# transfer.net
KiCad netlist of a schematic drawn in EAGLE
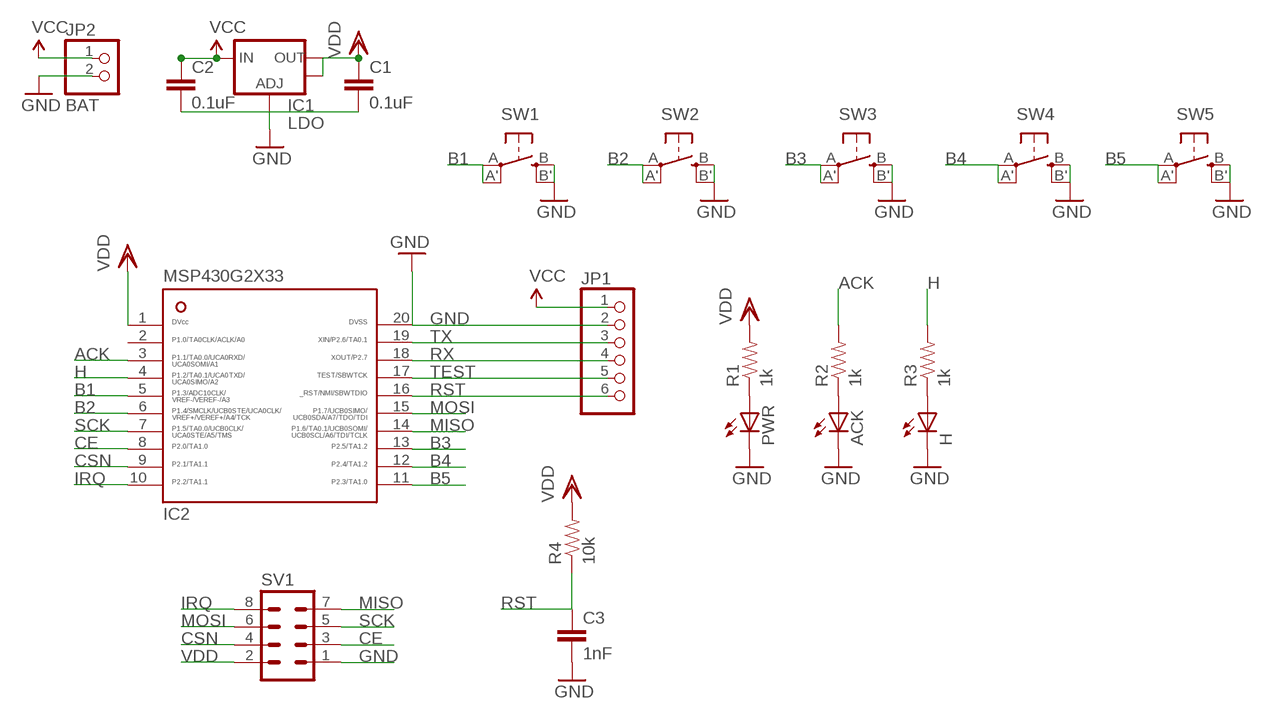
[diagram p0: schematic, sheet 1]

(export (version "E")
  (design (tool "Eeschema 10.0.6"))
  (components
    (comp (ref "ACK")
      (value "LEDCHIP-LED0805")
      (footprint "eagle-import:CHIP-LED0805")
      (libsource (lib "eagle-import") (part "LEDCHIP-LED0805"))
    )
    (comp (ref "C1")
      (value "0.1uF")
      (footprint "eagle-import:0603-CAP")
      (libsource (lib "eagle-import") (part "0.1UF-25V(+80/-20%)(0603)"))
    )
    (comp (ref "C2")
      (value "0.1uF")
      (footprint "eagle-import:0603-CAP")
      (libsource (lib "eagle-import") (part "0.1UF-25V(+80/-20%)(0603)"))
    )
    (comp (ref "C3")
      (value "1nF")
      (footprint "eagle-import:0603-CAP")
      (libsource (lib "eagle-import") (part "0.1UF-25V(+80/-20%)(0603)"))
    )
    (comp (ref "H")
      (value "LEDCHIP-LED0805")
      (footprint "eagle-import:CHIP-LED0805")
      (libsource (lib "eagle-import") (part "LEDCHIP-LED0805"))
    )
    (comp (ref "IC1")
      (value "LDO")
      (footprint "eagle-import:SOT223")
      (libsource (lib "eagle-import") (part "V_REG_LM1117SOT223"))
    )
    (comp (ref "IC2")
      (value "MSP430")
      (footprint "eagle-import:PW20")
      (libsource (lib "eagle-import") (part "MSP430G2X33-20PW20"))
    )
    (comp (ref "JP1")
      (value "PINHD-1X6")
      (footprint "eagle-import:1X06")
      (libsource (lib "eagle-import") (part "PINHD-1X6"))
    )
    (comp (ref "JP2")
      (value "BAT")
      (footprint "eagle-import:1X02")
      (libsource (lib "eagle-import") (part "PINHD-1X2"))
    )
    (comp (ref "PWR")
      (value "LEDCHIP-LED0805")
      (footprint "eagle-import:CHIP-LED0805")
      (libsource (lib "eagle-import") (part "LEDCHIP-LED0805"))
    )
    (comp (ref "R1")
      (value "1k")
      (footprint "eagle-import:0805")
      (libsource (lib "eagle-import") (part "0.22OHM1/4W1%(0805)"))
    )
    (comp (ref "R2")
      (value "1k")
      (footprint "eagle-import:0805")
      (libsource (lib "eagle-import") (part "0.22OHM1/4W1%(0805)"))
    )
    (comp (ref "R3")
      (value "1k")
      (footprint "eagle-import:0805")
      (libsource (lib "eagle-import") (part "0.22OHM1/4W1%(0805)"))
    )
    (comp (ref "R4")
      (value "10k")
      (footprint "eagle-import:0805")
      (libsource (lib "eagle-import") (part "0.22OHM1/4W1%(0805)"))
    )
    (comp (ref "SV1")
      (value "MA04-2")
      (footprint "eagle-import:MA04-2")
      (libsource (lib "eagle-import") (part "MA04-2"))
    )
    (comp (ref "SW1")
      (value "SPST_TACT-EVQQ2")
      (footprint "eagle-import:EVQ-Q2")
      (libsource (lib "eagle-import") (part "SPST_TACT-EVQQ2"))
    )
    (comp (ref "SW2")
      (value "SPST_TACT-EVQQ2")
      (footprint "eagle-import:EVQ-Q2")
      (libsource (lib "eagle-import") (part "SPST_TACT-EVQQ2"))
    )
    (comp (ref "SW3")
      (value "SPST_TACT-EVQQ2")
      (footprint "eagle-import:EVQ-Q2")
      (libsource (lib "eagle-import") (part "SPST_TACT-EVQQ2"))
    )
    (comp (ref "SW4")
      (value "SPST_TACT-EVQQ2")
      (footprint "eagle-import:EVQ-Q2")
      (libsource (lib "eagle-import") (part "SPST_TACT-EVQQ2"))
    )
    (comp (ref "SW5")
      (value "SPST_TACT-EVQQ2")
      (footprint "eagle-import:EVQ-Q2")
      (libsource (lib "eagle-import") (part "SPST_TACT-EVQQ2"))
    )
  )
  (nets
    (net (code "1") (name "/ACK") (class "Default")
      (node (ref "IC2") (pin "3") (pinfunction "3_3") (pintype "bidirectional"))
      (node (ref "R2") (pin "2") (pinfunction "2_2") (pintype "passive"))
    )
    (net (code "2") (name "/B1") (class "Default")
      (node (ref "IC2") (pin "5") (pinfunction "5_5") (pintype "bidirectional"))
      (node (ref "SW1") (pin "A") (pinfunction "P_A") (pintype "passive"))
      (node (ref "SW1") (pin "A'") (pinfunction "P1_A'") (pintype "passive"))
    )
    (net (code "3") (name "/B2") (class "Default")
      (node (ref "IC2") (pin "6") (pinfunction "6_6") (pintype "bidirectional"))
      (node (ref "SW2") (pin "A") (pinfunction "P_A") (pintype "passive"))
      (node (ref "SW2") (pin "A'") (pinfunction "P1_A'") (pintype "passive"))
    )
    (net (code "4") (name "/B3") (class "Default")
      (node (ref "IC2") (pin "13") (pinfunction "13_13") (pintype "bidirectional"))
      (node (ref "SW3") (pin "A") (pinfunction "P_A") (pintype "passive"))
      (node (ref "SW3") (pin "A'") (pinfunction "P1_A'") (pintype "passive"))
    )
    (net (code "5") (name "/B4") (class "Default")
      (node (ref "IC2") (pin "12") (pinfunction "12_12") (pintype "bidirectional"))
      (node (ref "SW4") (pin "A") (pinfunction "P_A") (pintype "passive"))
      (node (ref "SW4") (pin "A'") (pinfunction "P1_A'") (pintype "passive"))
    )
    (net (code "6") (name "/B5") (class "Default")
      (node (ref "IC2") (pin "11") (pinfunction "11_11") (pintype "bidirectional"))
      (node (ref "SW5") (pin "A") (pinfunction "P_A") (pintype "passive"))
      (node (ref "SW5") (pin "A'") (pinfunction "P1_A'") (pintype "passive"))
    )
    (net (code "7") (name "/CE") (class "Default")
      (node (ref "IC2") (pin "8") (pinfunction "8_8") (pintype "bidirectional"))
      (node (ref "SV1") (pin "3") (pinfunction "3_3") (pintype "passive"))
    )
    (net (code "8") (name "/CSN") (class "Default")
      (node (ref "IC2") (pin "9") (pinfunction "9_9") (pintype "bidirectional"))
      (node (ref "SV1") (pin "4") (pinfunction "4_4") (pintype "passive"))
    )
    (net (code "9") (name "/H") (class "Default")
      (node (ref "IC2") (pin "4") (pinfunction "4_4") (pintype "bidirectional"))
      (node (ref "R3") (pin "2") (pinfunction "2_2") (pintype "passive"))
    )
    (net (code "10") (name "/IRQ") (class "Default")
      (node (ref "IC2") (pin "10") (pinfunction "10_10") (pintype "bidirectional"))
      (node (ref "SV1") (pin "8") (pinfunction "8_8") (pintype "passive"))
    )
    (net (code "11") (name "/MISO") (class "Default")
      (node (ref "IC2") (pin "14") (pinfunction "14_14") (pintype "bidirectional"))
      (node (ref "SV1") (pin "7") (pinfunction "7_7") (pintype "passive"))
    )
    (net (code "12") (name "/MOSI") (class "Default")
      (node (ref "IC2") (pin "15") (pinfunction "15_15") (pintype "bidirectional"))
      (node (ref "SV1") (pin "6") (pinfunction "6_6") (pintype "passive"))
    )
    (net (code "13") (name "/RST") (class "Default")
      (node (ref "C3") (pin "1") (pinfunction "1_1") (pintype "passive"))
      (node (ref "IC2") (pin "16") (pinfunction "16_16") (pintype "bidirectional"))
      (node (ref "JP1") (pin "6") (pinfunction "6_6") (pintype "passive"))
      (node (ref "R4") (pin "1") (pinfunction "1_1") (pintype "passive"))
    )
    (net (code "14") (name "/RX") (class "Default")
      (node (ref "IC2") (pin "18") (pinfunction "18_18") (pintype "bidirectional"))
      (node (ref "JP1") (pin "4") (pinfunction "4_4") (pintype "passive"))
    )
    (net (code "15") (name "/SCK") (class "Default")
      (node (ref "IC2") (pin "7") (pinfunction "7_7") (pintype "bidirectional"))
      (node (ref "SV1") (pin "5") (pinfunction "5_5") (pintype "passive"))
    )
    (net (code "16") (name "/TEST") (class "Default")
      (node (ref "IC2") (pin "17") (pinfunction "17_17") (pintype "bidirectional"))
      (node (ref "JP1") (pin "5") (pinfunction "5_5") (pintype "passive"))
    )
    (net (code "17") (name "/TX") (class "Default")
      (node (ref "IC2") (pin "19") (pinfunction "19_19") (pintype "bidirectional"))
      (node (ref "JP1") (pin "3") (pinfunction "3_3") (pintype "passive"))
    )
    (net (code "18") (name "GND") (class "Default")
      (node (ref "ACK") (pin "C") (pinfunction "C_C") (pintype "passive"))
      (node (ref "C1") (pin "2") (pinfunction "2_2") (pintype "passive"))
      (node (ref "C2") (pin "2") (pinfunction "2_2") (pintype "passive"))
      (node (ref "C3") (pin "2") (pinfunction "2_2") (pintype "passive"))
      (node (ref "H") (pin "C") (pinfunction "C_C") (pintype "passive"))
      (node (ref "IC1") (pin "1") (pinfunction "ADJ_1") (pintype "input"))
      (node (ref "IC2") (pin "20") (pinfunction "20_20") (pintype "bidirectional"))
      (node (ref "JP1") (pin "2") (pinfunction "2_2") (pintype "passive"))
      (node (ref "JP2") (pin "2") (pinfunction "2_2") (pintype "passive"))
      (node (ref "PWR") (pin "C") (pinfunction "C_C") (pintype "passive"))
      (node (ref "SV1") (pin "1") (pinfunction "1_1") (pintype "passive"))
      (node (ref "SW1") (pin "B") (pinfunction "S_B") (pintype "passive"))
      (node (ref "SW1") (pin "B'") (pinfunction "S1_B'") (pintype "passive"))
      (node (ref "SW2") (pin "B") (pinfunction "S_B") (pintype "passive"))
      (node (ref "SW2") (pin "B'") (pinfunction "S1_B'") (pintype "passive"))
      (node (ref "SW3") (pin "B") (pinfunction "S_B") (pintype "passive"))
      (node (ref "SW3") (pin "B'") (pinfunction "S1_B'") (pintype "passive"))
      (node (ref "SW4") (pin "B") (pinfunction "S_B") (pintype "passive"))
      (node (ref "SW4") (pin "B'") (pinfunction "S1_B'") (pintype "passive"))
      (node (ref "SW5") (pin "B") (pinfunction "S_B") (pintype "passive"))
      (node (ref "SW5") (pin "B'") (pinfunction "S1_B'") (pintype "passive"))
    )
    (net (code "19") (name "Net-(ACK-PadA)") (class "Default")
      (node (ref "ACK") (pin "A") (pinfunction "A_A") (pintype "passive"))
      (node (ref "R2") (pin "1") (pinfunction "1_1") (pintype "passive"))
    )
    (net (code "20") (name "Net-(H-PadA)") (class "Default")
      (node (ref "H") (pin "A") (pinfunction "A_A") (pintype "passive"))
      (node (ref "R3") (pin "1") (pinfunction "1_1") (pintype "passive"))
    )
    (net (code "21") (name "Net-(PWR-PadA)") (class "Default")
      (node (ref "PWR") (pin "A") (pinfunction "A_A") (pintype "passive"))
      (node (ref "R1") (pin "1") (pinfunction "1_1") (pintype "passive"))
    )
    (net (code "22") (name "VCC") (class "Default")
      (node (ref "C2") (pin "1") (pinfunction "1_1") (pintype "passive"))
      (node (ref "IC1") (pin "3") (pinfunction "IN_3") (pintype "input"))
      (node (ref "JP1") (pin "1") (pinfunction "1_1") (pintype "passive"))
      (node (ref "JP2") (pin "1") (pinfunction "1_1") (pintype "passive"))
    )
    (net (code "23") (name "VDD") (class "Default")
      (node (ref "C1") (pin "1") (pinfunction "1_1") (pintype "passive"))
      (node (ref "IC1") (pin "2") (pinfunction "OUT_2") (pintype "output"))
      (node (ref "IC1") (pin "4") (pinfunction "OUT_4") (pintype "output"))
      (node (ref "IC2") (pin "1") (pinfunction "1_1") (pintype "bidirectional"))
      (node (ref "R1") (pin "2") (pinfunction "2_2") (pintype "passive"))
      (node (ref "R4") (pin "2") (pinfunction "2_2") (pintype "passive"))
      (node (ref "SV1") (pin "2") (pinfunction "2_2") (pintype "passive"))
    )
    (net (code "24") (name "unconnected-(IC2-Pad2)") (class "Default")
      (node (ref "IC2") (pin "2") (pinfunction "2_2") (pintype "bidirectional"))
    )
  )
)
